# ESP32.net
KiCad netlist of a schematic drawn in Altium Designer
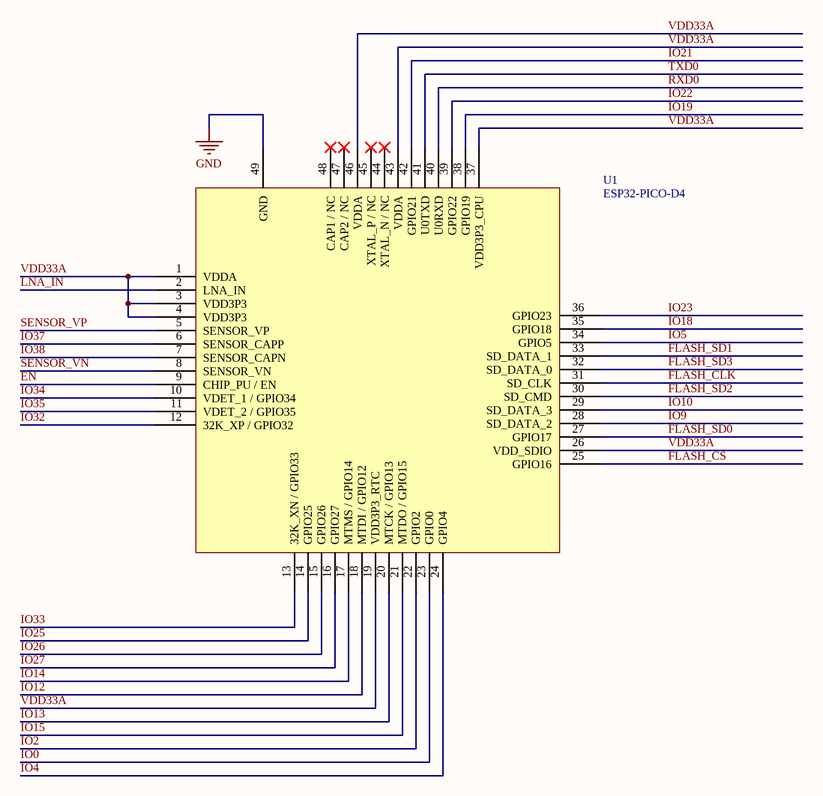
[diagram p0: ESP32.SchDoc]

(export (version "E")
  (design (tool "Eeschema 10.0.6"))
  (components
    (comp (ref "U1")
      (value "ESP32-PICO-D4")
      (footprint "ESP32-PICO-D4")
      (description "RF TRANSCEIVER ICS QFN-48_7X7X05P ROHS")
      (fields (field (name "MANUFACTURER") "Espressif Systems") (field (name "LCSC PART #") "C193707"))
      (libsource (lib "ESP32") (part "ESP32-PICO-D4"))
    )
  )
  (nets
    (net (code "1") (name "/EN") (class "Default")
      (node (ref "U1") (pin "9") (pinfunction "CHIP_PU_/_EN_9") (pintype "passive"))
    )
    (net (code "2") (name "/FLASH_CLK") (class "Default")
      (node (ref "U1") (pin "31") (pinfunction "SD_CLK_31") (pintype "passive"))
    )
    (net (code "3") (name "/FLASH_CS") (class "Default")
      (node (ref "U1") (pin "25") (pinfunction "GPIO16_25") (pintype "passive"))
    )
    (net (code "4") (name "/FLASH_SD0") (class "Default")
      (node (ref "U1") (pin "27") (pinfunction "GPIO17_27") (pintype "passive"))
    )
    (net (code "5") (name "/FLASH_SD1") (class "Default")
      (node (ref "U1") (pin "33") (pinfunction "SD_DATA_1_33") (pintype "passive"))
    )
    (net (code "6") (name "/FLASH_SD2") (class "Default")
      (node (ref "U1") (pin "30") (pinfunction "SD_CMD_30") (pintype "passive"))
    )
    (net (code "7") (name "/FLASH_SD3") (class "Default")
      (node (ref "U1") (pin "32") (pinfunction "SD_DATA_0_32") (pintype "passive"))
    )
    (net (code "8") (name "/IO0") (class "Default")
      (node (ref "U1") (pin "23") (pinfunction "GPIO0_23") (pintype "passive"))
    )
    (net (code "9") (name "/IO2") (class "Default")
      (node (ref "U1") (pin "22") (pinfunction "GPIO2_22") (pintype "passive"))
    )
    (net (code "10") (name "/IO4") (class "Default")
      (node (ref "U1") (pin "24") (pinfunction "GPIO4_24") (pintype "passive"))
    )
    (net (code "11") (name "/IO5") (class "Default")
      (node (ref "U1") (pin "34") (pinfunction "GPIO5_34") (pintype "passive"))
    )
    (net (code "12") (name "/IO9") (class "Default")
      (node (ref "U1") (pin "28") (pinfunction "SD_DATA_2_28") (pintype "passive"))
    )
    (net (code "13") (name "/IO10") (class "Default")
      (node (ref "U1") (pin "29") (pinfunction "SD_DATA_3_29") (pintype "passive"))
    )
    (net (code "14") (name "/IO12") (class "Default")
      (node (ref "U1") (pin "18") (pinfunction "MTDI_/_GPIO12_18") (pintype "passive"))
    )
    (net (code "15") (name "/IO13") (class "Default")
      (node (ref "U1") (pin "20") (pinfunction "MTCK_/_GPIO13_20") (pintype "passive"))
    )
    (net (code "16") (name "/IO14") (class "Default")
      (node (ref "U1") (pin "17") (pinfunction "MTMS_/_GPIO14_17") (pintype "passive"))
    )
    (net (code "17") (name "/IO15") (class "Default")
      (node (ref "U1") (pin "21") (pinfunction "MTDO_/_GPIO15_21") (pintype "passive"))
    )
    (net (code "18") (name "/IO18") (class "Default")
      (node (ref "U1") (pin "35") (pinfunction "GPIO18_35") (pintype "passive"))
    )
    (net (code "19") (name "/IO19") (class "Default")
      (node (ref "U1") (pin "38") (pinfunction "GPIO19_38") (pintype "passive"))
    )
    (net (code "20") (name "/IO21") (class "Default")
      (node (ref "U1") (pin "42") (pinfunction "GPIO21_42") (pintype "passive"))
    )
    (net (code "21") (name "/IO22") (class "Default")
      (node (ref "U1") (pin "39") (pinfunction "GPIO22_39") (pintype "passive"))
    )
    (net (code "22") (name "/IO23") (class "Default")
      (node (ref "U1") (pin "36") (pinfunction "GPIO23_36") (pintype "passive"))
    )
    (net (code "23") (name "/IO25") (class "Default")
      (node (ref "U1") (pin "14") (pinfunction "GPIO25_14") (pintype "passive"))
    )
    (net (code "24") (name "/IO26") (class "Default")
      (node (ref "U1") (pin "15") (pinfunction "GPIO26_15") (pintype "passive"))
    )
    (net (code "25") (name "/IO27") (class "Default")
      (node (ref "U1") (pin "16") (pinfunction "GPIO27_16") (pintype "passive"))
    )
    (net (code "26") (name "/IO32") (class "Default")
      (node (ref "U1") (pin "12") (pinfunction "32K_XP_/_GPIO32_12") (pintype "passive"))
    )
    (net (code "27") (name "/IO33") (class "Default")
      (node (ref "U1") (pin "13") (pinfunction "32K_XN_/_GPIO33_13") (pintype "passive"))
    )
    (net (code "28") (name "/IO34") (class "Default")
      (node (ref "U1") (pin "10") (pinfunction "VDET_1_/_GPIO34_10") (pintype "passive"))
    )
    (net (code "29") (name "/IO35") (class "Default")
      (node (ref "U1") (pin "11") (pinfunction "VDET_2_/_GPIO35_11") (pintype "passive"))
    )
    (net (code "30") (name "/IO37") (class "Default")
      (node (ref "U1") (pin "6") (pinfunction "SENSOR_CAPP_6") (pintype "passive"))
    )
    (net (code "31") (name "/IO38") (class "Default")
      (node (ref "U1") (pin "7") (pinfunction "SENSOR_CAPN_7") (pintype "passive"))
    )
    (net (code "32") (name "/LNA_IN") (class "Default")
      (node (ref "U1") (pin "2") (pinfunction "LNA_IN_2") (pintype "passive"))
    )
    (net (code "33") (name "/RXD0") (class "Default")
      (node (ref "U1") (pin "40") (pinfunction "U0RXD_40") (pintype "passive"))
    )
    (net (code "34") (name "/SENSOR_VN") (class "Default")
      (node (ref "U1") (pin "8") (pinfunction "SENSOR_VN_8") (pintype "passive"))
    )
    (net (code "35") (name "/SENSOR_VP") (class "Default")
      (node (ref "U1") (pin "5") (pinfunction "SENSOR_VP_5") (pintype "passive"))
    )
    (net (code "36") (name "/TXD0") (class "Default")
      (node (ref "U1") (pin "41") (pinfunction "U0TXD_41") (pintype "passive"))
    )
    (net (code "37") (name "/VDD33A") (class "Default")
      (node (ref "U1") (pin "1") (pinfunction "VDDA_1") (pintype "passive"))
      (node (ref "U1") (pin "19") (pinfunction "VDD3P3_RTC_19") (pintype "passive"))
      (node (ref "U1") (pin "26") (pinfunction "VDD_SDIO_26") (pintype "passive"))
      (node (ref "U1") (pin "3") (pinfunction "VDD3P3_3") (pintype "passive"))
      (node (ref "U1") (pin "37") (pinfunction "VDD3P3_CPU_37") (pintype "passive"))
      (node (ref "U1") (pin "4") (pinfunction "VDD3P3_4") (pintype "passive"))
      (node (ref "U1") (pin "43") (pinfunction "VDDA_43") (pintype "passive"))
      (node (ref "U1") (pin "46") (pinfunction "VDDA_46") (pintype "passive"))
    )
    (net (code "38") (name "GND") (class "Default")
      (node (ref "U1") (pin "49") (pinfunction "GND_49") (pintype "passive"))
    )
    (net (code "39") (name "unconnected-(U1-CAP1_{slash}_NC-Pad48)") (class "Default")
      (node (ref "U1") (pin "48") (pinfunction "CAP1_/_NC_48") (pintype "passive+no_connect"))
    )
    (net (code "40") (name "unconnected-(U1-CAP2_{slash}_NC-Pad47)") (class "Default")
      (node (ref "U1") (pin "47") (pinfunction "CAP2_/_NC_47") (pintype "passive+no_connect"))
    )
    (net (code "41") (name "unconnected-(U1-XTAL_N_{slash}_NC-Pad44)") (class "Default")
      (node (ref "U1") (pin "44") (pinfunction "XTAL_N_/_NC_44") (pintype "passive+no_connect"))
    )
    (net (code "42") (name "unconnected-(U1-XTAL_P_{slash}_NC-Pad45)") (class "Default")
      (node (ref "U1") (pin "45") (pinfunction "XTAL_P_/_NC_45") (pintype "passive+no_connect"))
    )
  )
)
